# haasoscope_pro_preinput_board.net
KiCad netlist of a schematic drawn in EAGLE
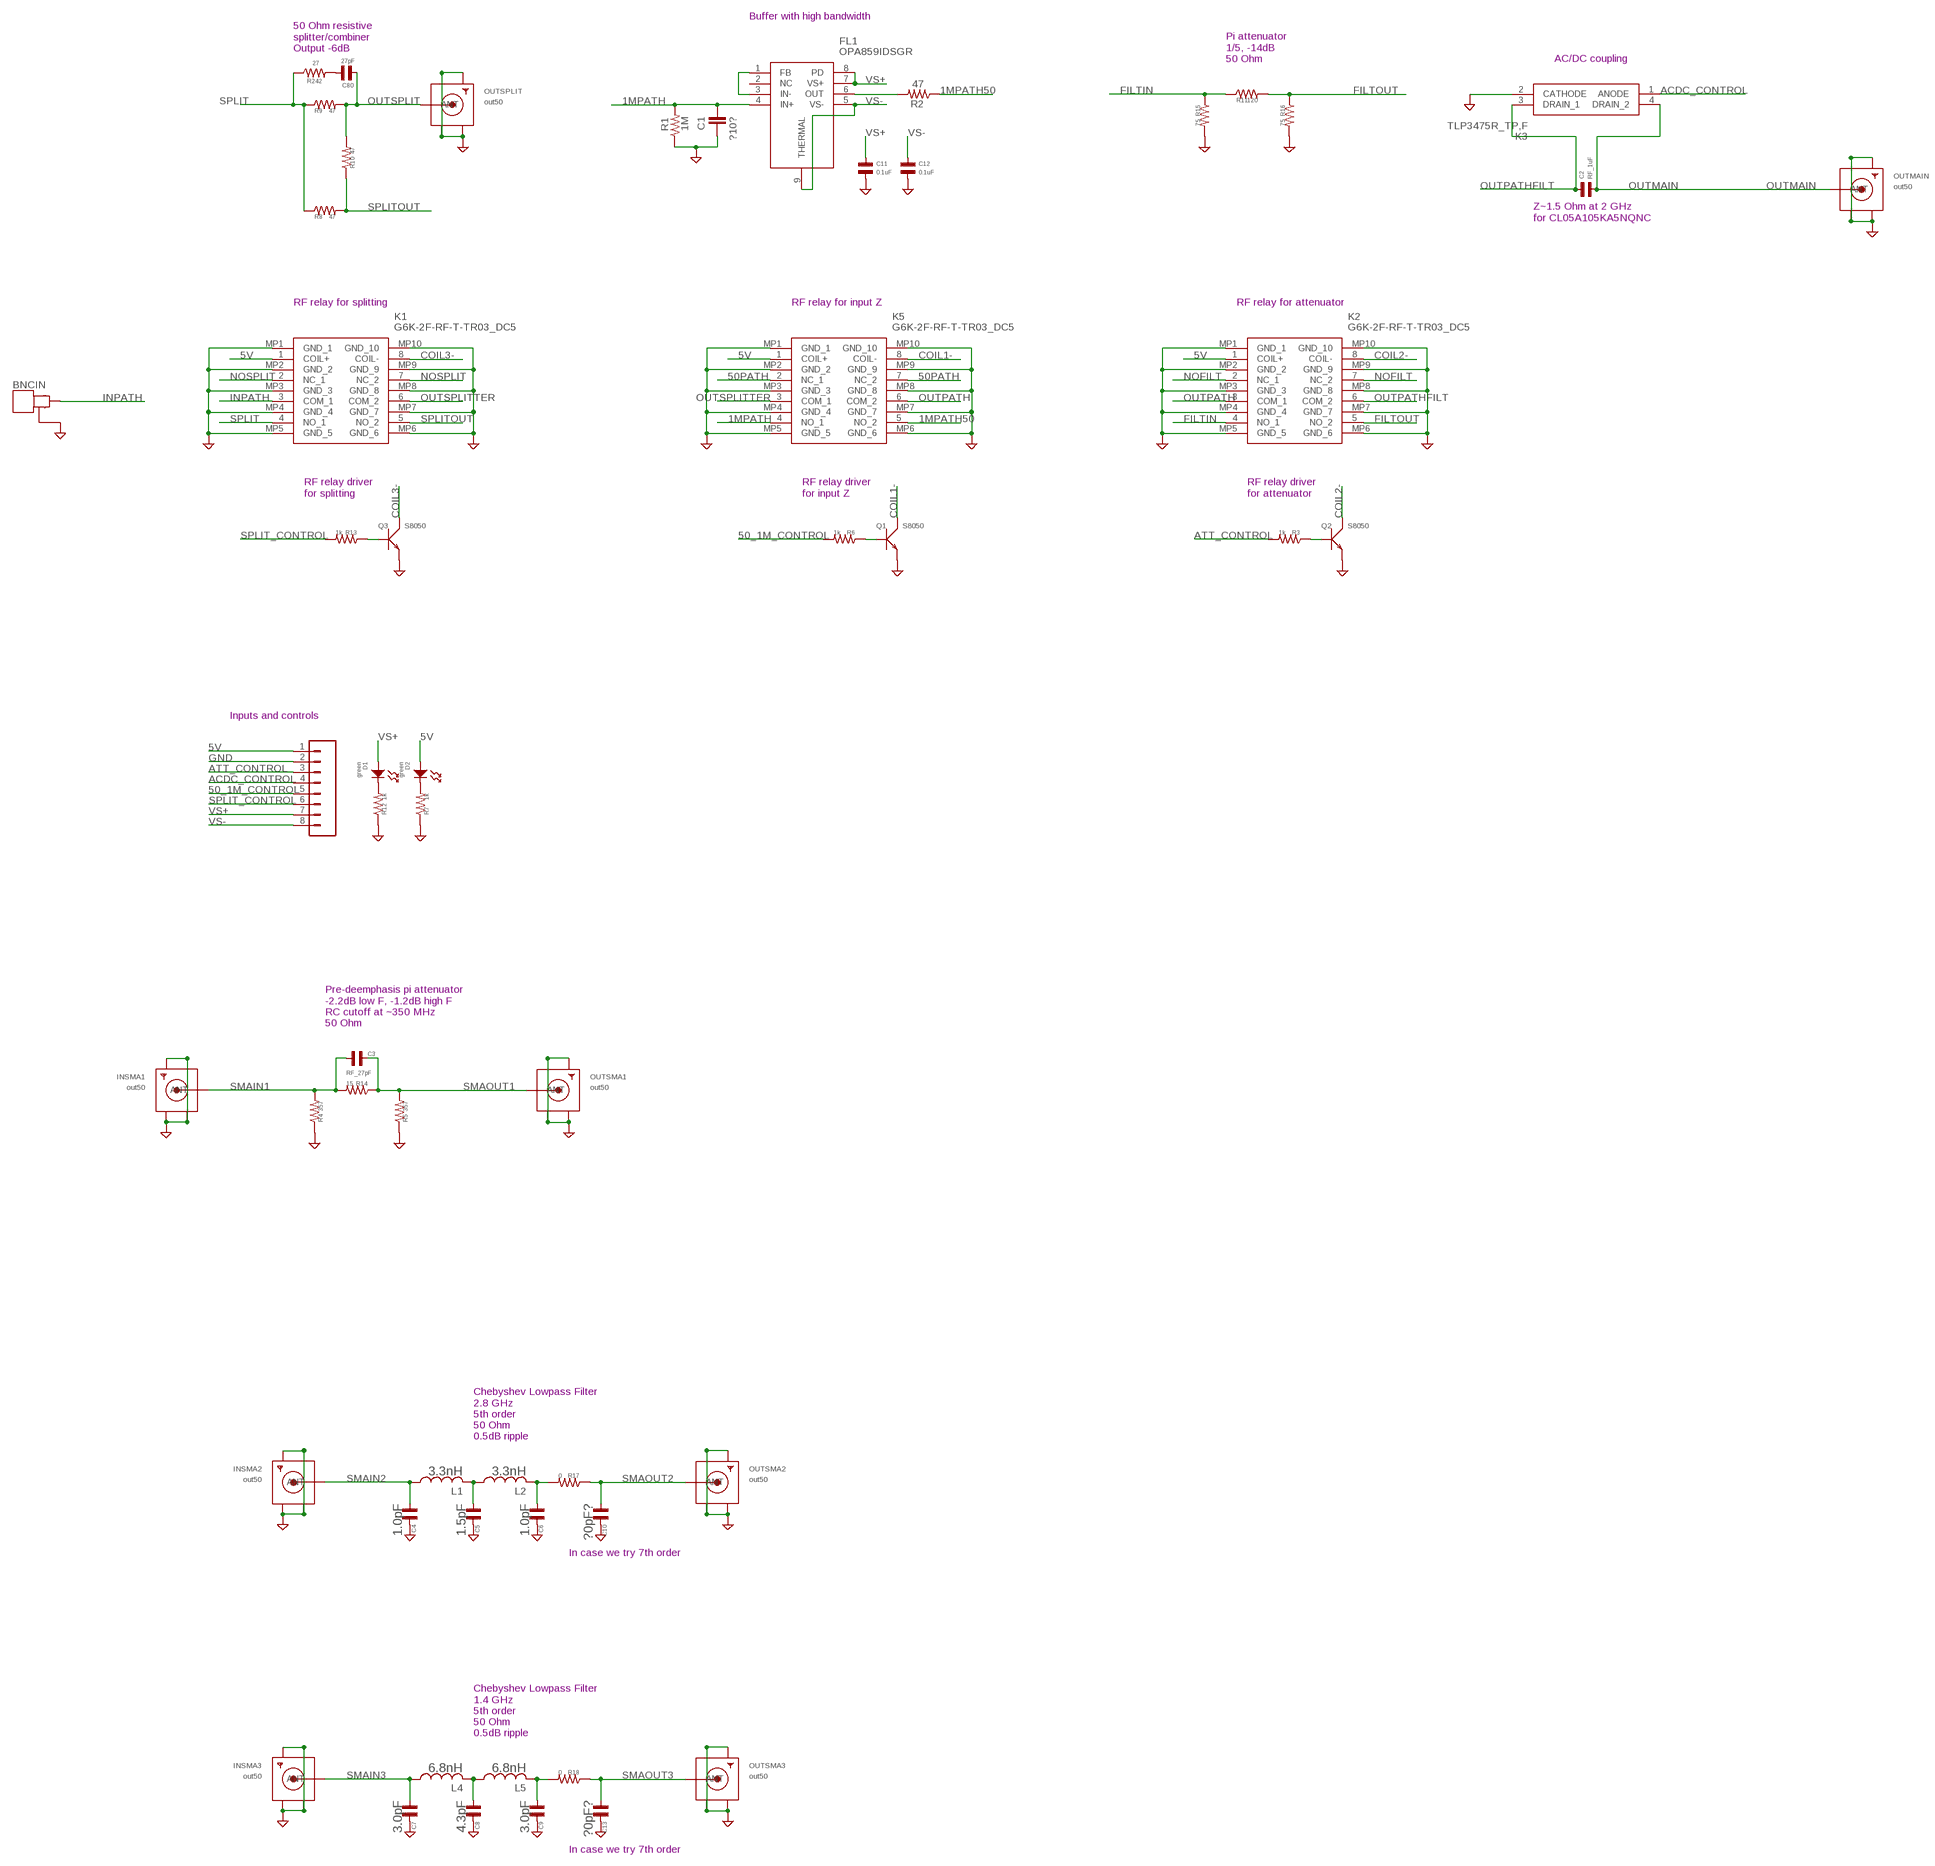
[diagram p0: schematic, sheet 1]

(export (version "E")
  (design (tool "Eeschema 10.0.6"))
  (components
    (comp (ref "BNCIN")
      (value "MOLEX_BNC_73100-0105")
      (footprint "eagle-import:MOLEX-BNC-73100-0105")
      (fields (field (name "MPN") "73100-0105"))
      (libsource (lib "eagle-import") (part "MOLEX_BNC_73100-0105"))
    )
    (comp (ref "C1")
      (value "?10?")
      (footprint "eagle-import:C0805")
      (libsource (lib "eagle-import") (part "C-EUC0805"))
    )
    (comp (ref "C2")
      (value "RF_1uF")
      (footprint "eagle-import:C0402")
      (libsource (lib "eagle-import") (part "CAPACITOR_NP_0402"))
    )
    (comp (ref "C3")
      (value "RF_27pF")
      (footprint "eagle-import:C0402")
      (libsource (lib "eagle-import") (part "CAPACITOR_NP_0402"))
    )
    (comp (ref "C4")
      (value "1.0pF")
      (footprint "eagle-import:C0402")
      (libsource (lib "eagle-import") (part "CAPACITOR_NP_0402"))
    )
    (comp (ref "C5")
      (value "1.5pF")
      (footprint "eagle-import:C0402")
      (libsource (lib "eagle-import") (part "CAPACITOR_NP_0402"))
    )
    (comp (ref "C6")
      (value "1.0pF")
      (footprint "eagle-import:C0402")
      (libsource (lib "eagle-import") (part "CAPACITOR_NP_0402"))
    )
    (comp (ref "C7")
      (value "3.0pF")
      (footprint "eagle-import:C0402")
      (libsource (lib "eagle-import") (part "CAPACITOR_NP_0402"))
    )
    (comp (ref "C8")
      (value "4.3pF")
      (footprint "eagle-import:C0402")
      (libsource (lib "eagle-import") (part "CAPACITOR_NP_0402"))
    )
    (comp (ref "C9")
      (value "3.0pF")
      (footprint "eagle-import:C0402")
      (libsource (lib "eagle-import") (part "CAPACITOR_NP_0402"))
    )
    (comp (ref "C10")
      (value "?0pF?")
      (footprint "eagle-import:C0402")
      (libsource (lib "eagle-import") (part "CAPACITOR_NP_0402"))
    )
    (comp (ref "C11")
      (value "0.1uF")
      (footprint "eagle-import:C0402")
      (libsource (lib "eagle-import") (part "CAPACITOR_NP_0402"))
    )
    (comp (ref "C12")
      (value "0.1uF")
      (footprint "eagle-import:C0402")
      (libsource (lib "eagle-import") (part "CAPACITOR_NP_0402"))
    )
    (comp (ref "C13")
      (value "?0pF?")
      (footprint "eagle-import:C0402")
      (libsource (lib "eagle-import") (part "CAPACITOR_NP_0402"))
    )
    (comp (ref "C80")
      (value "27pF")
      (footprint "eagle-import:C0402")
      (libsource (lib "eagle-import") (part "CAPACITOR_NP_0402"))
    )
    (comp (ref "D1")
      (value "green")
      (footprint "eagle-import:LED0603")
      (fields (field (name "HOUSEPART") "NO"))
      (libsource (lib "eagle-import") (part "LED_SINGLE-0603"))
    )
    (comp (ref "D2")
      (value "green")
      (footprint "eagle-import:LED0603")
      (fields (field (name "HOUSEPART") "NO"))
      (libsource (lib "eagle-import") (part "LED_SINGLE-0603"))
    )
    (comp (ref "FL1")
      (value "OPA859IDSGR")
      (footprint "eagle-import:SON50P200X200X80-9N")
      (fields (field (name "MOUSER_PART_NUMBER") "595-OPA859IDSGR"))
      (libsource (lib "eagle-import") (part "OPA859IDSGR"))
    )
    (comp (ref "INSMA1")
      (value "out50")
      (footprint "eagle-import:SMA_EDGELAUNCH")
      (libsource (lib "eagle-import") (part "SMACONNECTOR_EDGE"))
    )
    (comp (ref "INSMA2")
      (value "out50")
      (footprint "eagle-import:SMA_EDGELAUNCH")
      (libsource (lib "eagle-import") (part "SMACONNECTOR_EDGE"))
    )
    (comp (ref "INSMA3")
      (value "out50")
      (footprint "eagle-import:SMA_EDGELAUNCH")
      (libsource (lib "eagle-import") (part "SMACONNECTOR_EDGE"))
    )
    (comp (ref "J4")
      (value "8pin")
      (footprint "eagle-import:1X08")
      (libsource (lib "eagle-import") (part "CONN_08{dblquote}"))
    )
    (comp (ref "K1")
      (value "G6K-2F-RF-T-TR03_DC5")
      (footprint "eagle-import:G6K2FRFTTR03DC5")
      (fields
        (field (name "MANUFACTURER_PART_NUMBER") "G6K-2F-RF-T-TR03 DC5")
        (field (name "MOUSER_PART_NUMBER") "653-G6K2FRFTTR03DC5")
      )
      (libsource (lib "eagle-import") (part "G6K-2F-RF-T-TR03_DC5"))
    )
    (comp (ref "K2")
      (value "G6K-2F-RF-T-TR03_DC5")
      (footprint "eagle-import:G6K2FRFTTR03DC5")
      (fields
        (field (name "MANUFACTURER_PART_NUMBER") "G6K-2F-RF-T-TR03 DC5")
        (field (name "MOUSER_PART_NUMBER") "653-G6K2FRFTTR03DC5")
      )
      (libsource (lib "eagle-import") (part "G6K-2F-RF-T-TR03_DC5"))
    )
    (comp (ref "K3")
      (value "TLP3475R_TP,F")
      (footprint "eagle-import:TLP3475RTPF")
      (fields
        (field (name "MANUFACTURER_PART_NUMBER") "TLP3475R(TP,F")
        (field (name "MOUSER_PART_NUMBER") "757-TLP3475RTPF")
        (field (name "MANUFACTURER_PART_NUMBER_1") "TLP3475R(TP,F")
      )
      (libsource (lib "eagle-import") (part "TLP3475R_TP,F"))
    )
    (comp (ref "K5")
      (value "G6K-2F-RF-T-TR03_DC5")
      (footprint "eagle-import:G6K2FRFTTR03DC5")
      (fields
        (field (name "MANUFACTURER_PART_NUMBER") "G6K-2F-RF-T-TR03 DC5")
        (field (name "MOUSER_PART_NUMBER") "653-G6K2FRFTTR03DC5")
      )
      (libsource (lib "eagle-import") (part "G6K-2F-RF-T-TR03_DC5"))
    )
    (comp (ref "L1")
      (value "3.3nH")
      (footprint "eagle-import:RESC0402_N")
      (libsource (lib "eagle-import") (part "INDUCTOR_0402_N"))
    )
    (comp (ref "L2")
      (value "3.3nH")
      (footprint "eagle-import:RESC0402_N")
      (libsource (lib "eagle-import") (part "INDUCTOR_0402_N"))
    )
    (comp (ref "L4")
      (value "6.8nH")
      (footprint "eagle-import:RESC0402_N")
      (libsource (lib "eagle-import") (part "INDUCTOR_0402_N"))
    )
    (comp (ref "L5")
      (value "6.8nH")
      (footprint "eagle-import:RESC0402_N")
      (libsource (lib "eagle-import") (part "INDUCTOR_0402_N"))
    )
    (comp (ref "OUTMAIN")
      (value "out50")
      (footprint "eagle-import:SMA_EDGELAUNCH")
      (libsource (lib "eagle-import") (part "SMACONNECTOR_EDGE"))
    )
    (comp (ref "OUTSMA1")
      (value "out50")
      (footprint "eagle-import:SMA_EDGELAUNCH")
      (libsource (lib "eagle-import") (part "SMACONNECTOR_EDGE"))
    )
    (comp (ref "OUTSMA2")
      (value "out50")
      (footprint "eagle-import:SMA_EDGELAUNCH")
      (libsource (lib "eagle-import") (part "SMACONNECTOR_EDGE"))
    )
    (comp (ref "OUTSMA3")
      (value "out50")
      (footprint "eagle-import:SMA_EDGELAUNCH")
      (libsource (lib "eagle-import") (part "SMACONNECTOR_EDGE"))
    )
    (comp (ref "OUTSPLIT")
      (value "out50")
      (footprint "eagle-import:SMA_EDGELAUNCH")
      (libsource (lib "eagle-import") (part "SMACONNECTOR_EDGE"))
    )
    (comp (ref "Q1")
      (value "S8050")
      (footprint "eagle-import:SOT-23")
      (libsource (lib "eagle-import") (part "SMD-TRANSISTORS-NPN-25V-500MW-S8050(SOT-23)"))
    )
    (comp (ref "Q2")
      (value "S8050")
      (footprint "eagle-import:SOT-23")
      (libsource (lib "eagle-import") (part "SMD-TRANSISTORS-NPN-25V-500MW-S8050(SOT-23)"))
    )
    (comp (ref "Q3")
      (value "S8050")
      (footprint "eagle-import:SOT-23")
      (libsource (lib "eagle-import") (part "SMD-TRANSISTORS-NPN-25V-500MW-S8050(SOT-23)"))
    )
    (comp (ref "R1")
      (value "1M")
      (footprint "eagle-import:R0805")
      (libsource (lib "eagle-import") (part "R-US_R0805"))
    )
    (comp (ref "R2")
      (value "47")
      (footprint "eagle-import:R0805")
      (libsource (lib "eagle-import") (part "R-US_R0805"))
    )
    (comp (ref "R3")
      (value "1k")
      (footprint "eagle-import:R0402")
      (libsource (lib "eagle-import") (part "RESISTOR_0402"))
    )
    (comp (ref "R4")
      (value "357")
      (footprint "eagle-import:R0402")
      (libsource (lib "eagle-import") (part "RESISTOR_0402"))
    )
    (comp (ref "R5")
      (value "357")
      (footprint "eagle-import:R0402")
      (libsource (lib "eagle-import") (part "RESISTOR_0402"))
    )
    (comp (ref "R6")
      (value "1k")
      (footprint "eagle-import:R0402")
      (libsource (lib "eagle-import") (part "RESISTOR_0402"))
    )
    (comp (ref "R7")
      (value "1k")
      (footprint "eagle-import:R0402")
      (libsource (lib "eagle-import") (part "RESISTOR_0402"))
    )
    (comp (ref "R8")
      (value "47")
      (footprint "eagle-import:R0402")
      (libsource (lib "eagle-import") (part "RESISTOR_0402"))
    )
    (comp (ref "R9")
      (value "47")
      (footprint "eagle-import:R0402")
      (libsource (lib "eagle-import") (part "RESISTOR_0402"))
    )
    (comp (ref "R10")
      (value "47")
      (footprint "eagle-import:R0402")
      (libsource (lib "eagle-import") (part "RESISTOR_0402"))
    )
    (comp (ref "R11")
      (value "120")
      (footprint "eagle-import:R0402")
      (libsource (lib "eagle-import") (part "RESISTOR_0402"))
    )
    (comp (ref "R12")
      (value "1k")
      (footprint "eagle-import:R0402")
      (libsource (lib "eagle-import") (part "RESISTOR_0402"))
    )
    (comp (ref "R13")
      (value "1k")
      (footprint "eagle-import:R0402")
      (libsource (lib "eagle-import") (part "RESISTOR_0402"))
    )
    (comp (ref "R14")
      (value "15")
      (footprint "eagle-import:R0402")
      (libsource (lib "eagle-import") (part "RESISTOR_0402"))
    )
    (comp (ref "R15")
      (value "75")
      (footprint "eagle-import:R0402")
      (libsource (lib "eagle-import") (part "RESISTOR_0402"))
    )
    (comp (ref "R16")
      (value "75")
      (footprint "eagle-import:R0402")
      (libsource (lib "eagle-import") (part "RESISTOR_0402"))
    )
    (comp (ref "R17")
      (value "0")
      (footprint "eagle-import:R0402")
      (libsource (lib "eagle-import") (part "RESISTOR_0402"))
    )
    (comp (ref "R18")
      (value "0")
      (footprint "eagle-import:R0402")
      (libsource (lib "eagle-import") (part "RESISTOR_0402"))
    )
    (comp (ref "R242")
      (value "27")
      (footprint "eagle-import:R0402")
      (libsource (lib "eagle-import") (part "RESISTOR_0402"))
    )
  )
  (nets
    (net (code "1") (name "/1MPATH") (class "Default")
      (node (ref "C1") (pin "2") (pinfunction "2_2") (pintype "passive"))
      (node (ref "FL1") (pin "4") (pinfunction "IN+_4") (pintype "input"))
      (node (ref "K5") (pin "4") (pinfunction "NO_1_4") (pintype "bidirectional"))
      (node (ref "R1") (pin "2") (pinfunction "2_2") (pintype "passive"))
    )
    (net (code "2") (name "/1MPATH50") (class "Default")
      (node (ref "K5") (pin "5") (pinfunction "NO_2_5") (pintype "bidirectional"))
      (node (ref "R2") (pin "1") (pinfunction "1_1") (pintype "passive"))
    )
    (net (code "3") (name "/5V") (class "Default")
      (node (ref "D2") (pin "ANODE") (pinfunction "ANODE_ANODE") (pintype "power_in"))
      (node (ref "J4") (pin "1") (pinfunction "1_1") (pintype "passive"))
      (node (ref "K1") (pin "1") (pinfunction "COIL+_1") (pintype "bidirectional"))
      (node (ref "K2") (pin "1") (pinfunction "COIL+_1") (pintype "bidirectional"))
      (node (ref "K5") (pin "1") (pinfunction "COIL+_1") (pintype "bidirectional"))
    )
    (net (code "4") (name "/50PATH") (class "Default")
      (node (ref "K5") (pin "2") (pinfunction "NC_1_2") (pintype "bidirectional"))
      (node (ref "K5") (pin "7") (pinfunction "NC_2_7") (pintype "bidirectional"))
    )
    (net (code "5") (name "/50_1M_CONTROL") (class "Default")
      (node (ref "J4") (pin "5") (pinfunction "5_5") (pintype "passive"))
      (node (ref "R6") (pin "P$2") (pinfunction "P$2_P$2") (pintype "passive"))
    )
    (net (code "6") (name "/ACDC_CONTROL") (class "Default")
      (node (ref "J4") (pin "4") (pinfunction "4_4") (pintype "passive"))
      (node (ref "K3") (pin "1") (pinfunction "ANODE_1") (pintype "bidirectional"))
    )
    (net (code "7") (name "/ATT_CONTROL") (class "Default")
      (node (ref "J4") (pin "3") (pinfunction "3_3") (pintype "passive"))
      (node (ref "R3") (pin "P$2") (pinfunction "P$2_P$2") (pintype "passive"))
    )
    (net (code "8") (name "/COIL1-") (class "Default")
      (node (ref "K5") (pin "8") (pinfunction "COIL-_8") (pintype "bidirectional"))
      (node (ref "Q1") (pin "3") (pinfunction "C_3") (pintype "passive"))
    )
    (net (code "9") (name "/COIL2-") (class "Default")
      (node (ref "K2") (pin "8") (pinfunction "COIL-_8") (pintype "bidirectional"))
      (node (ref "Q2") (pin "3") (pinfunction "C_3") (pintype "passive"))
    )
    (net (code "10") (name "/COIL3-") (class "Default")
      (node (ref "K1") (pin "8") (pinfunction "COIL-_8") (pintype "bidirectional"))
      (node (ref "Q3") (pin "3") (pinfunction "C_3") (pintype "passive"))
    )
    (net (code "11") (name "/FILTIN") (class "Default")
      (node (ref "K2") (pin "4") (pinfunction "NO_1_4") (pintype "bidirectional"))
      (node (ref "R11") (pin "P$1") (pinfunction "P$1_P$1") (pintype "passive"))
      (node (ref "R15") (pin "P$1") (pinfunction "P$1_P$1") (pintype "passive"))
    )
    (net (code "12") (name "/FILTOUT") (class "Default")
      (node (ref "K2") (pin "5") (pinfunction "NO_2_5") (pintype "bidirectional"))
      (node (ref "R11") (pin "P$2") (pinfunction "P$2_P$2") (pintype "passive"))
      (node (ref "R16") (pin "P$1") (pinfunction "P$1_P$1") (pintype "passive"))
    )
    (net (code "13") (name "/INPATH") (class "Default")
      (node (ref "BNCIN") (pin "SIGNAL") (pinfunction "SIGNAL_SIGNAL") (pintype "bidirectional"))
      (node (ref "K1") (pin "3") (pinfunction "COM_1_3") (pintype "bidirectional"))
    )
    (net (code "14") (name "/NOFILT") (class "Default")
      (node (ref "K2") (pin "2") (pinfunction "NC_1_2") (pintype "bidirectional"))
      (node (ref "K2") (pin "7") (pinfunction "NC_2_7") (pintype "bidirectional"))
    )
    (net (code "15") (name "/NOSPLIT") (class "Default")
      (node (ref "K1") (pin "2") (pinfunction "NC_1_2") (pintype "bidirectional"))
      (node (ref "K1") (pin "7") (pinfunction "NC_2_7") (pintype "bidirectional"))
    )
    (net (code "16") (name "/OUTMAIN") (class "Default")
      (node (ref "C2") (pin "P$2") (pinfunction "P$2_P$2") (pintype "passive"))
      (node (ref "K3") (pin "4") (pinfunction "DRAIN_2_4") (pintype "bidirectional"))
      (node (ref "OUTMAIN") (pin "P") (pinfunction "ANT_P") (pintype "bidirectional"))
    )
    (net (code "17") (name "/OUTPATH") (class "Default")
      (node (ref "K2") (pin "3") (pinfunction "COM_1_3") (pintype "bidirectional"))
      (node (ref "K5") (pin "6") (pinfunction "COM_2_6") (pintype "bidirectional"))
    )
    (net (code "18") (name "/OUTPATHFILT") (class "Default")
      (node (ref "C2") (pin "P$1") (pinfunction "P$1_P$1") (pintype "passive"))
      (node (ref "K2") (pin "6") (pinfunction "COM_2_6") (pintype "bidirectional"))
      (node (ref "K3") (pin "3") (pinfunction "DRAIN_1_3") (pintype "bidirectional"))
    )
    (net (code "19") (name "/OUTSPLIT") (class "Default")
      (node (ref "C80") (pin "P$2") (pinfunction "P$2_P$2") (pintype "passive"))
      (node (ref "OUTSPLIT") (pin "P") (pinfunction "ANT_P") (pintype "bidirectional"))
      (node (ref "R10") (pin "P$2") (pinfunction "P$2_P$2") (pintype "passive"))
      (node (ref "R9") (pin "P$2") (pinfunction "P$2_P$2") (pintype "passive"))
    )
    (net (code "20") (name "/OUTSPLITTER") (class "Default")
      (node (ref "K1") (pin "6") (pinfunction "COM_2_6") (pintype "bidirectional"))
      (node (ref "K5") (pin "3") (pinfunction "COM_1_3") (pintype "bidirectional"))
    )
    (net (code "21") (name "/SMAIN1") (class "Default")
      (node (ref "C3") (pin "P$1") (pinfunction "P$1_P$1") (pintype "passive"))
      (node (ref "INSMA1") (pin "P") (pinfunction "ANT_P") (pintype "bidirectional"))
      (node (ref "R14") (pin "P$2") (pinfunction "P$2_P$2") (pintype "passive"))
      (node (ref "R4") (pin "P$2") (pinfunction "P$2_P$2") (pintype "passive"))
    )
    (net (code "22") (name "/SMAIN2") (class "Default")
      (node (ref "C4") (pin "P$1") (pinfunction "P$1_P$1") (pintype "passive"))
      (node (ref "INSMA2") (pin "P") (pinfunction "ANT_P") (pintype "bidirectional"))
      (node (ref "L1") (pin "1") (pinfunction "1_1") (pintype "passive"))
    )
    (net (code "23") (name "/SMAIN3") (class "Default")
      (node (ref "C7") (pin "P$1") (pinfunction "P$1_P$1") (pintype "passive"))
      (node (ref "INSMA3") (pin "P") (pinfunction "ANT_P") (pintype "bidirectional"))
      (node (ref "L4") (pin "1") (pinfunction "1_1") (pintype "passive"))
    )
    (net (code "24") (name "/SMAOUT1") (class "Default")
      (node (ref "C3") (pin "P$2") (pinfunction "P$2_P$2") (pintype "passive"))
      (node (ref "OUTSMA1") (pin "P") (pinfunction "ANT_P") (pintype "bidirectional"))
      (node (ref "R14") (pin "P$1") (pinfunction "P$1_P$1") (pintype "passive"))
      (node (ref "R5") (pin "P$2") (pinfunction "P$2_P$2") (pintype "passive"))
    )
    (net (code "25") (name "/SMAOUT2") (class "Default")
      (node (ref "C10") (pin "P$1") (pinfunction "P$1_P$1") (pintype "passive"))
      (node (ref "OUTSMA2") (pin "P") (pinfunction "ANT_P") (pintype "bidirectional"))
      (node (ref "R17") (pin "P$1") (pinfunction "P$1_P$1") (pintype "passive"))
    )
    (net (code "26") (name "/SMAOUT3") (class "Default")
      (node (ref "C13") (pin "P$1") (pinfunction "P$1_P$1") (pintype "passive"))
      (node (ref "OUTSMA3") (pin "P") (pinfunction "ANT_P") (pintype "bidirectional"))
      (node (ref "R18") (pin "P$1") (pinfunction "P$1_P$1") (pintype "passive"))
    )
    (net (code "27") (name "/SPLIT") (class "Default")
      (node (ref "K1") (pin "4") (pinfunction "NO_1_4") (pintype "bidirectional"))
      (node (ref "R242") (pin "P$1") (pinfunction "P$1_P$1") (pintype "passive"))
      (node (ref "R8") (pin "P$1") (pinfunction "P$1_P$1") (pintype "passive"))
      (node (ref "R9") (pin "P$1") (pinfunction "P$1_P$1") (pintype "passive"))
    )
    (net (code "28") (name "/SPLITOUT") (class "Default")
      (node (ref "K1") (pin "5") (pinfunction "NO_2_5") (pintype "bidirectional"))
      (node (ref "R10") (pin "P$1") (pinfunction "P$1_P$1") (pintype "passive"))
      (node (ref "R8") (pin "P$2") (pinfunction "P$2_P$2") (pintype "passive"))
    )
    (net (code "29") (name "/SPLIT_CONTROL") (class "Default")
      (node (ref "J4") (pin "6") (pinfunction "6_6") (pintype "passive"))
      (node (ref "R13") (pin "P$2") (pinfunction "P$2_P$2") (pintype "passive"))
    )
    (net (code "30") (name "/VS+") (class "Default")
      (node (ref "C11") (pin "P$1") (pinfunction "P$1_P$1") (pintype "passive"))
      (node (ref "D1") (pin "ANODE") (pinfunction "ANODE_ANODE") (pintype "power_in"))
      (node (ref "FL1") (pin "7") (pinfunction "VS+_7") (pintype "power_in"))
      (node (ref "FL1") (pin "8") (pinfunction "PD_8") (pintype "input"))
      (node (ref "J4") (pin "7") (pinfunction "7_7") (pintype "passive"))
    )
    (net (code "31") (name "/VS-") (class "Default")
      (node (ref "C12") (pin "P$1") (pinfunction "P$1_P$1") (pintype "passive"))
      (node (ref "FL1") (pin "5") (pinfunction "VS-_5") (pintype "power_in"))
      (node (ref "FL1") (pin "9") (pinfunction "THERMAL_9") (pintype "bidirectional"))
      (node (ref "J4") (pin "8") (pinfunction "8_8") (pintype "passive"))
    )
    (net (code "32") (name "GND") (class "Default")
      (node (ref "BNCIN") (pin "GND1") (pinfunction "GND_GND1") (pintype "bidirectional"))
      (node (ref "BNCIN") (pin "GND2") (pinfunction "GND_GND2") (pintype "bidirectional"))
      (node (ref "C1") (pin "1") (pinfunction "1_1") (pintype "passive"))
      (node (ref "C10") (pin "P$2") (pinfunction "P$2_P$2") (pintype "passive"))
      (node (ref "C11") (pin "P$2") (pinfunction "P$2_P$2") (pintype "passive"))
      (node (ref "C12") (pin "P$2") (pinfunction "P$2_P$2") (pintype "passive"))
      (node (ref "C13") (pin "P$2") (pinfunction "P$2_P$2") (pintype "passive"))
      (node (ref "C4") (pin "P$2") (pinfunction "P$2_P$2") (pintype "passive"))
      (node (ref "C5") (pin "P$2") (pinfunction "P$2_P$2") (pintype "passive"))
      (node (ref "C6") (pin "P$2") (pinfunction "P$2_P$2") (pintype "passive"))
      (node (ref "C7") (pin "P$2") (pinfunction "P$2_P$2") (pintype "passive"))
      (node (ref "C8") (pin "P$2") (pinfunction "P$2_P$2") (pintype "passive"))
      (node (ref "C9") (pin "P$2") (pinfunction "P$2_P$2") (pintype "passive"))
      (node (ref "INSMA1") (pin "GND@1") (pinfunction "GND4_GND@1") (pintype "power_in"))
      (node (ref "INSMA1") (pin "GND@2") (pinfunction "GND3_GND@2") (pintype "power_in"))
      (node (ref "INSMA1") (pin "GND@3") (pinfunction "GND2_GND@3") (pintype "power_in"))
      (node (ref "INSMA1") (pin "GND@4") (pinfunction "GND1_GND@4") (pintype "power_in"))
      (node (ref "INSMA2") (pin "GND@1") (pinfunction "GND4_GND@1") (pintype "power_in"))
      (node (ref "INSMA2") (pin "GND@2") (pinfunction "GND3_GND@2") (pintype "power_in"))
      (node (ref "INSMA2") (pin "GND@3") (pinfunction "GND2_GND@3") (pintype "power_in"))
      (node (ref "INSMA2") (pin "GND@4") (pinfunction "GND1_GND@4") (pintype "power_in"))
      (node (ref "INSMA3") (pin "GND@1") (pinfunction "GND4_GND@1") (pintype "power_in"))
      (node (ref "INSMA3") (pin "GND@2") (pinfunction "GND3_GND@2") (pintype "power_in"))
      (node (ref "INSMA3") (pin "GND@3") (pinfunction "GND2_GND@3") (pintype "power_in"))
      (node (ref "INSMA3") (pin "GND@4") (pinfunction "GND1_GND@4") (pintype "power_in"))
      (node (ref "J4") (pin "2") (pinfunction "2_2") (pintype "passive"))
      (node (ref "K1") (pin "MP1") (pinfunction "GND_1_MP1") (pintype "bidirectional"))
      (node (ref "K1") (pin "MP10") (pinfunction "GND_10_MP10") (pintype "bidirectional"))
      (node (ref "K1") (pin "MP2") (pinfunction "GND_2_MP2") (pintype "bidirectional"))
      (node (ref "K1") (pin "MP3") (pinfunction "GND_3_MP3") (pintype "bidirectional"))
      (node (ref "K1") (pin "MP4") (pinfunction "GND_4_MP4") (pintype "bidirectional"))
      (node (ref "K1") (pin "MP5") (pinfunction "GND_5_MP5") (pintype "bidirectional"))
      (node (ref "K1") (pin "MP6") (pinfunction "GND_6_MP6") (pintype "bidirectional"))
      (node (ref "K1") (pin "MP7") (pinfunction "GND_7_MP7") (pintype "bidirectional"))
      (node (ref "K1") (pin "MP8") (pinfunction "GND_8_MP8") (pintype "bidirectional"))
      (node (ref "K1") (pin "MP9") (pinfunction "GND_9_MP9") (pintype "bidirectional"))
      (node (ref "K2") (pin "MP1") (pinfunction "GND_1_MP1") (pintype "bidirectional"))
      (node (ref "K2") (pin "MP10") (pinfunction "GND_10_MP10") (pintype "bidirectional"))
      (node (ref "K2") (pin "MP2") (pinfunction "GND_2_MP2") (pintype "bidirectional"))
      (node (ref "K2") (pin "MP3") (pinfunction "GND_3_MP3") (pintype "bidirectional"))
      (node (ref "K2") (pin "MP4") (pinfunction "GND_4_MP4") (pintype "bidirectional"))
      (node (ref "K2") (pin "MP5") (pinfunction "GND_5_MP5") (pintype "bidirectional"))
      (node (ref "K2") (pin "MP6") (pinfunction "GND_6_MP6") (pintype "bidirectional"))
      (node (ref "K2") (pin "MP7") (pinfunction "GND_7_MP7") (pintype "bidirectional"))
      (node (ref "K2") (pin "MP8") (pinfunction "GND_8_MP8") (pintype "bidirectional"))
      (node (ref "K2") (pin "MP9") (pinfunction "GND_9_MP9") (pintype "bidirectional"))
      (node (ref "K3") (pin "2") (pinfunction "CATHODE_2") (pintype "bidirectional"))
      (node (ref "K5") (pin "MP1") (pinfunction "GND_1_MP1") (pintype "bidirectional"))
      (node (ref "K5") (pin "MP10") (pinfunction "GND_10_MP10") (pintype "bidirectional"))
      (node (ref "K5") (pin "MP2") (pinfunction "GND_2_MP2") (pintype "bidirectional"))
      (node (ref "K5") (pin "MP3") (pinfunction "GND_3_MP3") (pintype "bidirectional"))
      (node (ref "K5") (pin "MP4") (pinfunction "GND_4_MP4") (pintype "bidirectional"))
      (node (ref "K5") (pin "MP5") (pinfunction "GND_5_MP5") (pintype "bidirectional"))
      (node (ref "K5") (pin "MP6") (pinfunction "GND_6_MP6") (pintype "bidirectional"))
      (node (ref "K5") (pin "MP7") (pinfunction "GND_7_MP7") (pintype "bidirectional"))
      (node (ref "K5") (pin "MP8") (pinfunction "GND_8_MP8") (pintype "bidirectional"))
      (node (ref "K5") (pin "MP9") (pinfunction "GND_9_MP9") (pintype "bidirectional"))
      (node (ref "OUTMAIN") (pin "GND@1") (pinfunction "GND4_GND@1") (pintype "power_in"))
      (node (ref "OUTMAIN") (pin "GND@2") (pinfunction "GND3_GND@2") (pintype "power_in"))
      (node (ref "OUTMAIN") (pin "GND@3") (pinfunction "GND2_GND@3") (pintype "power_in"))
      (node (ref "OUTMAIN") (pin "GND@4") (pinfunction "GND1_GND@4") (pintype "power_in"))
      (node (ref "OUTSMA1") (pin "GND@1") (pinfunction "GND4_GND@1") (pintype "power_in"))
      (node (ref "OUTSMA1") (pin "GND@2") (pinfunction "GND3_GND@2") (pintype "power_in"))
      (node (ref "OUTSMA1") (pin "GND@3") (pinfunction "GND2_GND@3") (pintype "power_in"))
      (node (ref "OUTSMA1") (pin "GND@4") (pinfunction "GND1_GND@4") (pintype "power_in"))
      (node (ref "OUTSMA2") (pin "GND@1") (pinfunction "GND4_GND@1") (pintype "power_in"))
      (node (ref "OUTSMA2") (pin "GND@2") (pinfunction "GND3_GND@2") (pintype "power_in"))
      (node (ref "OUTSMA2") (pin "GND@3") (pinfunction "GND2_GND@3") (pintype "power_in"))
      (node (ref "OUTSMA2") (pin "GND@4") (pinfunction "GND1_GND@4") (pintype "power_in"))
      (node (ref "OUTSMA3") (pin "GND@1") (pinfunction "GND4_GND@1") (pintype "power_in"))
      (node (ref "OUTSMA3") (pin "GND@2") (pinfunction "GND3_GND@2") (pintype "power_in"))
      (node (ref "OUTSMA3") (pin "GND@3") (pinfunction "GND2_GND@3") (pintype "power_in"))
      (node (ref "OUTSMA3") (pin "GND@4") (pinfunction "GND1_GND@4") (pintype "power_in"))
      (node (ref "OUTSPLIT") (pin "GND@1") (pinfunction "GND4_GND@1") (pintype "power_in"))
      (node (ref "OUTSPLIT") (pin "GND@2") (pinfunction "GND3_GND@2") (pintype "power_in"))
      (node (ref "OUTSPLIT") (pin "GND@3") (pinfunction "GND2_GND@3") (pintype "power_in"))
      (node (ref "OUTSPLIT") (pin "GND@4") (pinfunction "GND1_GND@4") (pintype "power_in"))
      (node (ref "Q1") (pin "2") (pinfunction "E_2") (pintype "passive"))
      (node (ref "Q2") (pin "2") (pinfunction "E_2") (pintype "passive"))
      (node (ref "Q3") (pin "2") (pinfunction "E_2") (pintype "passive"))
      (node (ref "R1") (pin "1") (pinfunction "1_1") (pintype "passive"))
      (node (ref "R12") (pin "P$1") (pinfunction "P$1_P$1") (pintype "passive"))
      (node (ref "R15") (pin "P$2") (pinfunction "P$2_P$2") (pintype "passive"))
      (node (ref "R16") (pin "P$2") (pinfunction "P$2_P$2") (pintype "passive"))
      (node (ref "R4") (pin "P$1") (pinfunction "P$1_P$1") (pintype "passive"))
      (node (ref "R5") (pin "P$1") (pinfunction "P$1_P$1") (pintype "passive"))
      (node (ref "R7") (pin "P$1") (pinfunction "P$1_P$1") (pintype "passive"))
    )
    (net (code "33") (name "Net-(C5-PadP$1)") (class "Default")
      (node (ref "C5") (pin "P$1") (pinfunction "P$1_P$1") (pintype "passive"))
      (node (ref "L1") (pin "2") (pinfunction "2_2") (pintype "passive"))
      (node (ref "L2") (pin "1") (pinfunction "1_1") (pintype "passive"))
    )
    (net (code "34") (name "Net-(C6-PadP$1)") (class "Default")
      (node (ref "C6") (pin "P$1") (pinfunction "P$1_P$1") (pintype "passive"))
      (node (ref "L2") (pin "2") (pinfunction "2_2") (pintype "passive"))
      (node (ref "R17") (pin "P$2") (pinfunction "P$2_P$2") (pintype "passive"))
    )
    (net (code "35") (name "Net-(C8-PadP$1)") (class "Default")
      (node (ref "C8") (pin "P$1") (pinfunction "P$1_P$1") (pintype "passive"))
      (node (ref "L4") (pin "2") (pinfunction "2_2") (pintype "passive"))
      (node (ref "L5") (pin "1") (pinfunction "1_1") (pintype "passive"))
    )
    (net (code "36") (name "Net-(C9-PadP$1)") (class "Default")
      (node (ref "C9") (pin "P$1") (pinfunction "P$1_P$1") (pintype "passive"))
      (node (ref "L5") (pin "2") (pinfunction "2_2") (pintype "passive"))
      (node (ref "R18") (pin "P$2") (pinfunction "P$2_P$2") (pintype "passive"))
    )
    (net (code "37") (name "Net-(C80-PadP$1)") (class "Default")
      (node (ref "C80") (pin "P$1") (pinfunction "P$1_P$1") (pintype "passive"))
      (node (ref "R242") (pin "P$2") (pinfunction "P$2_P$2") (pintype "passive"))
    )
    (net (code "38") (name "Net-(D1-PadCATHODE)") (class "Default")
      (node (ref "D1") (pin "CATHODE") (pinfunction "CATHODE_CATHODE") (pintype "power_in"))
      (node (ref "R12") (pin "P$2") (pinfunction "P$2_P$2") (pintype "passive"))
    )
    (net (code "39") (name "Net-(D2-PadCATHODE)") (class "Default")
      (node (ref "D2") (pin "CATHODE") (pinfunction "CATHODE_CATHODE") (pintype "power_in"))
      (node (ref "R7") (pin "P$2") (pinfunction "P$2_P$2") (pintype "passive"))
    )
    (net (code "40") (name "Net-(FL1-FB)") (class "Default")
      (node (ref "FL1") (pin "1") (pinfunction "FB_1") (pintype "input"))
      (node (ref "FL1") (pin "3") (pinfunction "IN-_3") (pintype "input"))
    )
    (net (code "41") (name "Net-(FL1-OUT)") (class "Default")
      (node (ref "FL1") (pin "6") (pinfunction "OUT_6") (pintype "output"))
      (node (ref "R2") (pin "2") (pinfunction "2_2") (pintype "passive"))
    )
    (net (code "42") (name "Net-(Q1-B)") (class "Default")
      (node (ref "Q1") (pin "1") (pinfunction "B_1") (pintype "passive"))
      (node (ref "R6") (pin "P$1") (pinfunction "P$1_P$1") (pintype "passive"))
    )
    (net (code "43") (name "Net-(Q2-B)") (class "Default")
      (node (ref "Q2") (pin "1") (pinfunction "B_1") (pintype "passive"))
      (node (ref "R3") (pin "P$1") (pinfunction "P$1_P$1") (pintype "passive"))
    )
    (net (code "44") (name "Net-(Q3-B)") (class "Default")
      (node (ref "Q3") (pin "1") (pinfunction "B_1") (pintype "passive"))
      (node (ref "R13") (pin "P$1") (pinfunction "P$1_P$1") (pintype "passive"))
    )
    (net (code "45") (name "unconnected-(FL1-NC-Pad2)") (class "Default")
      (node (ref "FL1") (pin "2") (pinfunction "NC_2") (pintype "no_connect"))
    )
  )
)
